# main.net
KiCad netlist of a schematic drawn in Altium Designer
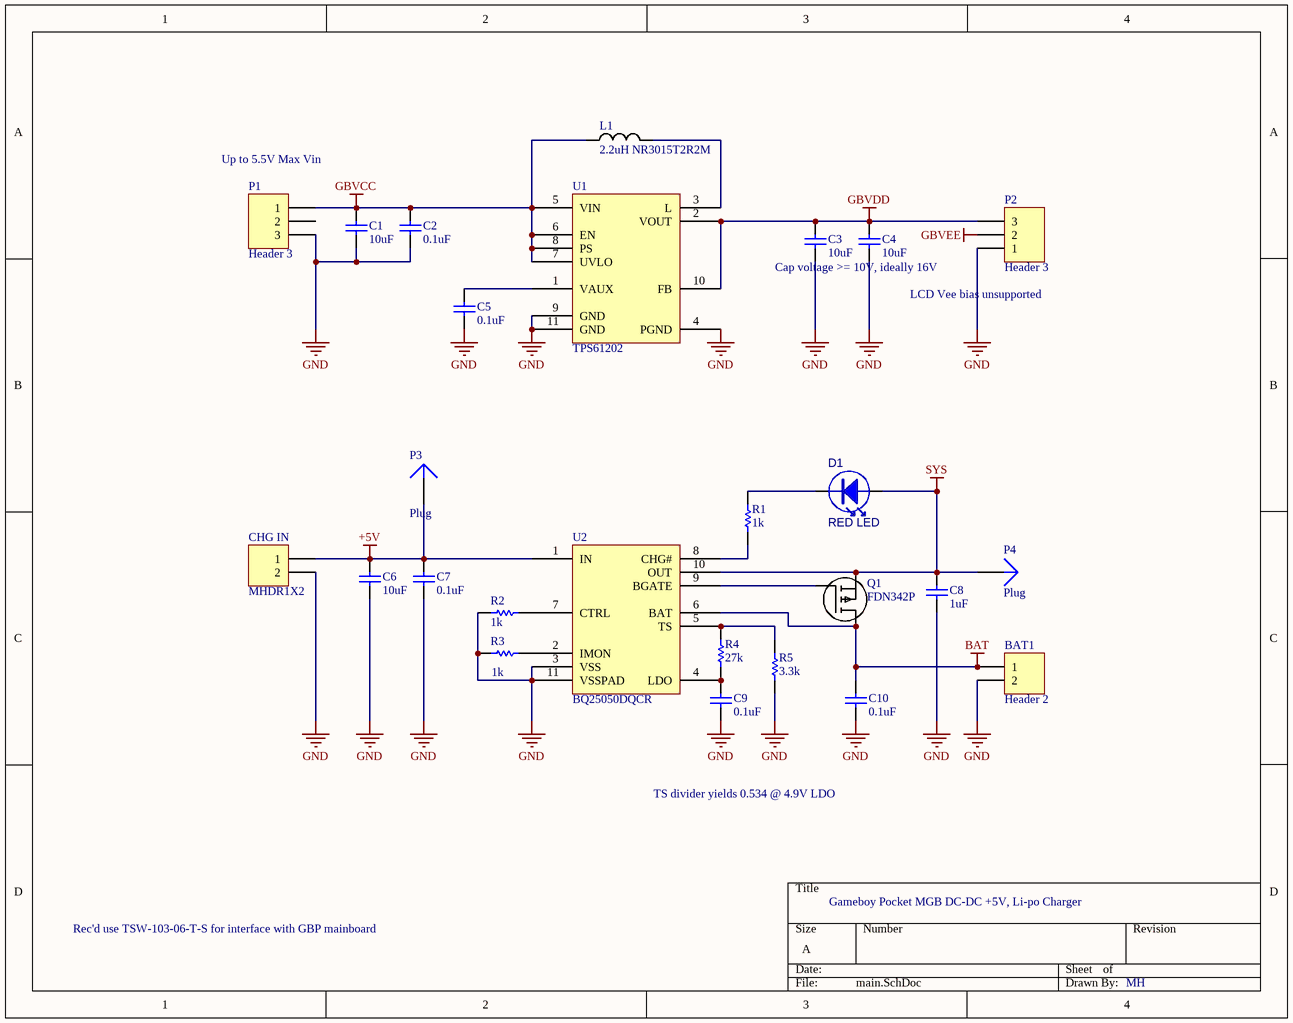
[diagram p0: main.SchDoc]

(export (version "E")
  (design (tool "Eeschema 10.0.6"))
  (components
    (comp (ref "BAT1")
      (value "Header 2")
      (footprint "HDR1X2")
      (description "Header, 2-Pin")
      (fields (field (name "PUBLISHER") "Altium Limited"))
      (libsource (lib "Miscellaneous Connectors") (part "Header 2"))
    )
    (comp (ref "C1")
      (value "10uF")
      (footprint "CAPC0805(2012)130_N")
      (description "Capacitor Ceramic")
      (libsource (lib "marsh") (part "CAP"))
    )
    (comp (ref "C2")
      (value "0.1uF")
      (footprint "CAPC0603(1608)100_N")
      (description "Capacitor Ceramic")
      (libsource (lib "marsh") (part "CAP"))
    )
    (comp (ref "C3")
      (value "10uF")
      (footprint "CAPC0805(2012)130_N")
      (description "Capacitor Ceramic")
      (libsource (lib "marsh") (part "CAP"))
    )
    (comp (ref "C4")
      (value "10uF")
      (footprint "CAPC0805(2012)130_N")
      (description "Capacitor Ceramic")
      (libsource (lib "marsh") (part "CAP"))
    )
    (comp (ref "C5")
      (value "0.1uF")
      (footprint "CAPC0603(1608)100_N")
      (description "Capacitor Ceramic")
      (libsource (lib "marsh") (part "CAP"))
    )
    (comp (ref "C6")
      (value "10uF")
      (footprint "CAPC0805(2012)130_N")
      (description "Capacitor Ceramic")
      (libsource (lib "marsh") (part "CAP"))
    )
    (comp (ref "C7")
      (value "0.1uF")
      (footprint "CAPC0603(1608)100_N")
      (description "Capacitor Ceramic")
      (libsource (lib "marsh") (part "CAP"))
    )
    (comp (ref "C8")
      (value "1uF")
      (footprint "CAPC0603(1608)100_N")
      (description "Capacitor Ceramic")
      (libsource (lib "marsh") (part "CAP"))
    )
    (comp (ref "C9")
      (value "0.1uF")
      (footprint "CAPC0603(1608)100_N")
      (description "Capacitor Ceramic")
      (libsource (lib "marsh") (part "CAP"))
    )
    (comp (ref "C10")
      (value "0.1uF")
      (footprint "CAPC0603(1608)100_N")
      (description "Capacitor Ceramic")
      (libsource (lib "marsh") (part "CAP"))
    )
    (comp (ref "CHG IN")
      (value "MHDR1X2")
      (footprint "MHDR1X2")
      (description "Header, 2-Pin")
      (fields (field (name "PUBLISHER") "Altium Limited"))
      (libsource (lib "Miscellaneous Connectors") (part "MHDR1X2"))
    )
    (comp (ref "D1")
      (value "RED LED")
      (footprint "LED_0603")
      (description "LED OPTO")
      (libsource (lib "marsh") (part "LED"))
    )
    (comp (ref "L1")
      (value "2.2uH NR3015T2R2M")
      (footprint "IND_3x3_SMD")
      (description "Power Inductor SMD")
      (libsource (lib "marsh") (part "IND_PWR"))
    )
    (comp (ref "P1")
      (value "Header 3")
      (footprint "HDR1X3")
      (description "Header, 3-Pin")
      (fields (field (name "PUBLISHER") "Altium Limited"))
      (libsource (lib "") (part "Header 3_1"))
    )
    (comp (ref "P2")
      (value "Header 3")
      (footprint "HDR1X3")
      (description "Header, 3-Pin")
      (fields (field (name "PUBLISHER") "Altium Limited"))
      (libsource (lib "Miscellaneous Connectors") (part "Header 3"))
    )
    (comp (ref "P3")
      (value "Plug")
      (footprint "PIN1")
      (fields (field (name "PUBLISHER") "Altium Limited"))
      (libsource (lib "Miscellaneous Connectors") (part "Plug"))
    )
    (comp (ref "P4")
      (value "Plug")
      (footprint "PIN1")
      (fields (field (name "PUBLISHER") "Altium Limited"))
      (libsource (lib "Miscellaneous Connectors") (part "Plug"))
    )
    (comp (ref "Q1")
      (value "FDN342P")
      (footprint "SOT-23")
      (description "P CHANNEL FET")
      (fields
        (field (name "MANUFACTURER") "Fairchild Semiconductor")
        (field (name "MANUFACTURER PART NUMBER") "2N7002")
      )
      (libsource (lib "marsh") (part "TRANSISTOR PCH FET"))
    )
    (comp (ref "R1")
      (value "1k")
      (footprint "RESC0603(1608)_N")
      (description "Resistor SMD")
      (libsource (lib "marsh") (part "RES"))
    )
    (comp (ref "R2")
      (value "1k")
      (footprint "RESC0603(1608)_N")
      (description "Resistor SMD")
      (libsource (lib "marsh") (part "RES"))
    )
    (comp (ref "R3")
      (value "1k")
      (footprint "RESC0603(1608)_N")
      (description "Resistor SMD")
      (libsource (lib "marsh") (part "RES"))
    )
    (comp (ref "R4")
      (value "27k")
      (footprint "RESC0603(1608)_N")
      (description "Resistor SMD")
      (libsource (lib "marsh") (part "RES"))
    )
    (comp (ref "R5")
      (value "3.3k")
      (footprint "RESC0603(1608)_N")
      (description "Resistor SMD")
      (libsource (lib "marsh") (part "RES"))
    )
    (comp (ref "U1")
      (value "TPS61202")
      (footprint "DRC10_TI")
      (description "Buck-Boost Regulator")
      (libsource (lib "marsh") (part "TPS61200"))
    )
    (comp (ref "U2")
      (value "BQ25050DQCR")
      (footprint "TI_WSON10")
      (description "IC BATT CHG LI-ION 1CELL 10WSON")
      (libsource (lib "marsh") (part "bq25050"))
    )
  )
  (nets
    (net (code "1") (name "+5V") (class "Default")
      (node (ref "C6") (pin "1") (pinfunction "1_1") (pintype "passive"))
      (node (ref "C7") (pin "1") (pinfunction "1_1") (pintype "passive"))
      (node (ref "CHG IN") (pin "1") (pinfunction "1_1") (pintype "passive"))
      (node (ref "P3") (pin "1") (pinfunction "1_1") (pintype "passive"))
      (node (ref "U2") (pin "1") (pinfunction "IN_1") (pintype "passive"))
    )
    (net (code "2") (name "BAT") (class "Default")
      (node (ref "BAT1") (pin "1") (pinfunction "1_1") (pintype "passive"))
      (node (ref "C10") (pin "1") (pinfunction "1_1") (pintype "passive"))
      (node (ref "Q1") (pin "3") (pintype "passive"))
      (node (ref "U2") (pin "6") (pinfunction "BAT_6") (pintype "passive"))
    )
    (net (code "3") (name "GBVCC") (class "Default")
      (node (ref "C1") (pin "1") (pinfunction "1_1") (pintype "passive"))
      (node (ref "C2") (pin "1") (pinfunction "1_1") (pintype "passive"))
      (node (ref "L1") (pin "1") (pinfunction "1_1") (pintype "passive"))
      (node (ref "P1") (pin "1") (pinfunction "1_1") (pintype "passive"))
      (node (ref "U1") (pin "5") (pinfunction "VIN_5") (pintype "passive"))
      (node (ref "U1") (pin "6") (pinfunction "EN_6") (pintype "passive"))
      (node (ref "U1") (pin "7") (pinfunction "UVLO_7") (pintype "passive"))
      (node (ref "U1") (pin "8") (pinfunction "PS_8") (pintype "passive"))
    )
    (net (code "4") (name "GBVDD") (class "Default")
      (node (ref "C3") (pin "1") (pinfunction "1_1") (pintype "passive"))
      (node (ref "C4") (pin "1") (pinfunction "1_1") (pintype "passive"))
      (node (ref "P2") (pin "3") (pinfunction "3_3") (pintype "passive"))
      (node (ref "U1") (pin "10") (pinfunction "FB_10") (pintype "passive"))
      (node (ref "U1") (pin "2") (pinfunction "VOUT_2") (pintype "passive"))
    )
    (net (code "5") (name "GBVEE") (class "Default")
      (node (ref "P2") (pin "2") (pinfunction "2_2") (pintype "passive"))
    )
    (net (code "6") (name "GND") (class "Default")
      (node (ref "BAT1") (pin "2") (pinfunction "2_2") (pintype "passive"))
      (node (ref "C1") (pin "2") (pinfunction "2_2") (pintype "passive"))
      (node (ref "C10") (pin "2") (pinfunction "2_2") (pintype "passive"))
      (node (ref "C2") (pin "2") (pinfunction "2_2") (pintype "passive"))
      (node (ref "C3") (pin "2") (pinfunction "2_2") (pintype "passive"))
      (node (ref "C4") (pin "2") (pinfunction "2_2") (pintype "passive"))
      (node (ref "C5") (pin "2") (pinfunction "2_2") (pintype "passive"))
      (node (ref "C6") (pin "2") (pinfunction "2_2") (pintype "passive"))
      (node (ref "C7") (pin "2") (pinfunction "2_2") (pintype "passive"))
      (node (ref "C8") (pin "2") (pinfunction "2_2") (pintype "passive"))
      (node (ref "C9") (pin "2") (pinfunction "2_2") (pintype "passive"))
      (node (ref "CHG IN") (pin "2") (pinfunction "2_2") (pintype "passive"))
      (node (ref "P1") (pin "3") (pinfunction "3_3") (pintype "passive"))
      (node (ref "P2") (pin "1") (pinfunction "1_1") (pintype "passive"))
      (node (ref "R2") (pin "2") (pinfunction "2_2") (pintype "passive"))
      (node (ref "R3") (pin "1") (pinfunction "1_1") (pintype "passive"))
      (node (ref "R5") (pin "1") (pinfunction "1_1") (pintype "passive"))
      (node (ref "U1") (pin "11") (pinfunction "GND_11") (pintype "passive"))
      (node (ref "U1") (pin "4") (pinfunction "PGND_4") (pintype "passive"))
      (node (ref "U1") (pin "9") (pinfunction "GND_9") (pintype "passive"))
      (node (ref "U2") (pin "11") (pinfunction "VSSPAD_11") (pintype "passive"))
      (node (ref "U2") (pin "3") (pinfunction "VSS_3") (pintype "passive"))
    )
    (net (code "7") (name "Net-(D1-K)") (class "Default")
      (node (ref "D1") (pin "1") (pinfunction "K_1") (pintype "passive"))
      (node (ref "R1") (pin "1") (pinfunction "1_1") (pintype "passive"))
    )
    (net (code "8") (name "Net-(U1-L)") (class "Default")
      (node (ref "L1") (pin "2") (pinfunction "2_2") (pintype "passive"))
      (node (ref "U1") (pin "3") (pinfunction "L_3") (pintype "passive"))
    )
    (net (code "9") (name "Net-(U1-VAUX)") (class "Default")
      (node (ref "C5") (pin "1") (pinfunction "1_1") (pintype "passive"))
      (node (ref "U1") (pin "1") (pinfunction "VAUX_1") (pintype "passive"))
    )
    (net (code "10") (name "Net-(U2-BGATE)") (class "Default")
      (node (ref "Q1") (pin "1") (pintype "passive"))
      (node (ref "U2") (pin "9") (pinfunction "BGATE_9") (pintype "passive"))
    )
    (net (code "11") (name "Net-(U2-CHG#)") (class "Default")
      (node (ref "R1") (pin "2") (pinfunction "2_2") (pintype "passive"))
      (node (ref "U2") (pin "8") (pinfunction "CHG#_8") (pintype "passive"))
    )
    (net (code "12") (name "Net-(U2-CTRL)") (class "Default")
      (node (ref "R2") (pin "1") (pinfunction "1_1") (pintype "passive"))
      (node (ref "U2") (pin "7") (pinfunction "CTRL_7") (pintype "passive"))
    )
    (net (code "13") (name "Net-(U2-IMON)") (class "Default")
      (node (ref "R3") (pin "2") (pinfunction "2_2") (pintype "passive"))
      (node (ref "U2") (pin "2") (pinfunction "IMON_2") (pintype "passive"))
    )
    (net (code "14") (name "Net-(U2-LDO)") (class "Default")
      (node (ref "C9") (pin "1") (pinfunction "1_1") (pintype "passive"))
      (node (ref "R4") (pin "2") (pinfunction "2_2") (pintype "passive"))
      (node (ref "U2") (pin "4") (pinfunction "LDO_4") (pintype "passive"))
    )
    (net (code "15") (name "Net-(U2-TS)") (class "Default")
      (node (ref "R4") (pin "1") (pinfunction "1_1") (pintype "passive"))
      (node (ref "R5") (pin "2") (pinfunction "2_2") (pintype "passive"))
      (node (ref "U2") (pin "5") (pinfunction "TS_5") (pintype "passive"))
    )
    (net (code "16") (name "SYS") (class "Default")
      (node (ref "C8") (pin "1") (pinfunction "1_1") (pintype "passive"))
      (node (ref "D1") (pin "2") (pinfunction "A_2") (pintype "passive"))
      (node (ref "P4") (pin "1") (pinfunction "1_1") (pintype "passive"))
      (node (ref "Q1") (pin "2") (pintype "passive"))
      (node (ref "U2") (pin "10") (pinfunction "OUT_10") (pintype "passive"))
    )
    (net (code "17") (name "unconnected-(P1-Pad2)") (class "Default")
      (node (ref "P1") (pin "2") (pinfunction "2_2") (pintype "passive"))
    )
  )
)
